# RedBeanSprout_Sch.net
KiCad netlist of a schematic drawn in Altium Designer
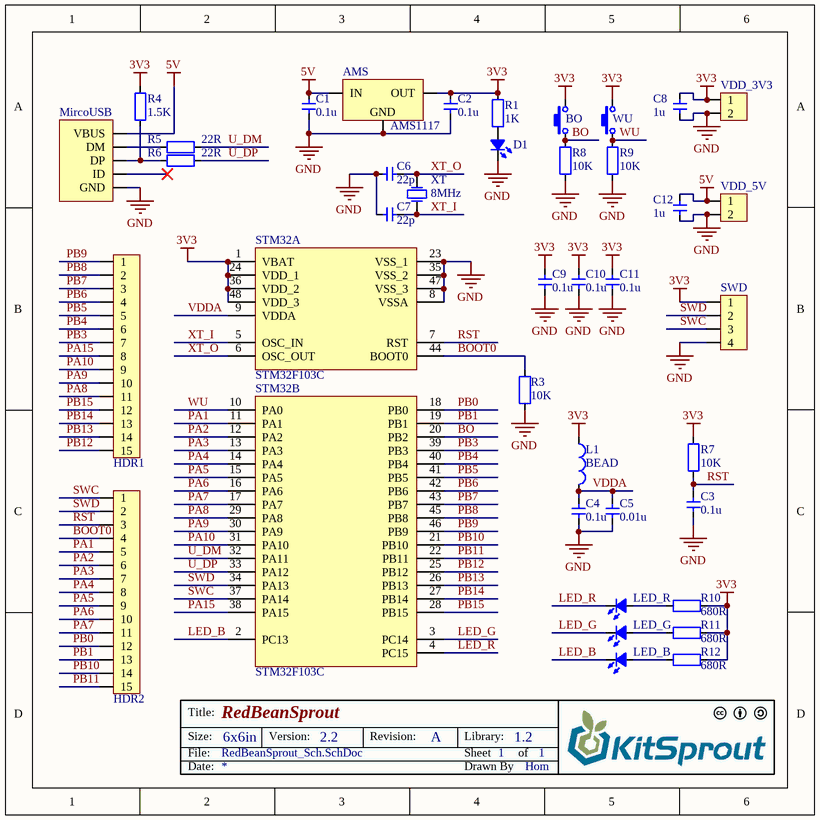
[diagram p0: RedBeanSprout_Sch.SchDoc]

(export (version "E")
  (design (tool "Eeschema 10.0.6"))
  (components
    (comp (ref "AMS")
      (value "AMS1117")
      (footprint "PCB_IntegratedCircuit:SOT223-3")
      (description "Power")
      (libsource (lib "SCH_IntegratedCircuit") (part "AMS1117"))
    )
    (comp (ref "BO")
      (value "ButtonTACT_3x6x2.5_180")
      (footprint "PCB_Switch:ButtonTACT_3x6x2.5_180")
      (description "Button")
      (libsource (lib "SCH_Switch") (part "ButtonTACT_3x6x2.5_180"))
    )
    (comp (ref "C1")
      (value "0.1u")
      (footprint "PCB_PassiveCap:CAP_0603")
      (description "Capacitor")
      (fields (field (name "Comment") "Cap_0603"))
      (libsource (lib "SCH_Passive") (part "Cap_0603"))
    )
    (comp (ref "C2")
      (value "0.1u")
      (footprint "PCB_PassiveCap:CAP_0603")
      (description "Capacitor")
      (fields (field (name "Comment") "Cap_0603"))
      (libsource (lib "SCH_Passive") (part "Cap_0603"))
    )
    (comp (ref "C3")
      (value "0.1u")
      (footprint "PCB_PassiveCap:CAP_0603")
      (description "Capacitor")
      (fields (field (name "Comment") "Cap_0603"))
      (libsource (lib "SCH_Passive") (part "Cap_0603"))
    )
    (comp (ref "C4")
      (value "0.1u")
      (footprint "PCB_PassiveCap:CAP_0603")
      (description "Capacitor")
      (fields (field (name "Comment") "Cap_0603"))
      (libsource (lib "SCH_Passive") (part "Cap_0603"))
    )
    (comp (ref "C5")
      (value "0.01u")
      (footprint "PCB_PassiveCap:CAP_0603")
      (description "Capacitor")
      (fields (field (name "Comment") "Cap_0603"))
      (libsource (lib "SCH_Passive") (part "Cap_0603"))
    )
    (comp (ref "C6")
      (value "22p")
      (footprint "PCB_PassiveCap:CAP_0603")
      (description "Capacitor")
      (fields (field (name "Comment") "Cap_0603"))
      (libsource (lib "SCH_Passive") (part "Cap_0603"))
    )
    (comp (ref "C7")
      (value "22p")
      (footprint "PCB_PassiveCap:CAP_0603")
      (description "Capacitor")
      (fields (field (name "Comment") "Cap_0603"))
      (libsource (lib "SCH_Passive") (part "Cap_0603"))
    )
    (comp (ref "C8")
      (value "1u")
      (footprint "PCB_PassiveCap:CAP_0603")
      (description "Capacitor")
      (fields (field (name "Comment") "Cap_0603"))
      (libsource (lib "SCH_Passive") (part "Cap_0603"))
    )
    (comp (ref "C9")
      (value "0.1u")
      (footprint "PCB_PassiveCap:CAP_0603")
      (description "Capacitor")
      (fields (field (name "Comment") "Cap_0603"))
      (libsource (lib "SCH_Passive") (part "Cap_0603"))
    )
    (comp (ref "C10")
      (value "0.1u")
      (footprint "PCB_PassiveCap:CAP_0603")
      (description "Capacitor")
      (fields (field (name "Comment") "Cap_0603"))
      (libsource (lib "SCH_Passive") (part "Cap_0603"))
    )
    (comp (ref "C11")
      (value "0.1u")
      (footprint "PCB_PassiveCap:CAP_0603")
      (description "Capacitor")
      (fields (field (name "Comment") "Cap_0603"))
      (libsource (lib "SCH_Passive") (part "Cap_0603"))
    )
    (comp (ref "C12")
      (value "1u")
      (footprint "PCB_PassiveCap:CAP_0603")
      (description "Capacitor")
      (fields (field (name "Comment") "Cap_0603"))
      (libsource (lib "SCH_Passive") (part "Cap_0603"))
    )
    (comp (ref "D1")
      (value "LED_0603")
      (footprint "PCB_ActiveLED:LED_0603_YELLOW")
      (description "LED")
      (libsource (lib "SCH_Active") (part "LED_0603"))
    )
    (comp (ref "HDR1")
      (value "HDR1x15_2.54")
      (footprint "PCB_ConnectorHDR:HDR1X15_2.54_180")
      (description "Header")
      (libsource (lib "SCH_ConnectorHDR") (part "HDR1x15_2.54"))
    )
    (comp (ref "HDR2")
      (value "HDR1x15_2.54")
      (footprint "PCB_ConnectorHDR:HDR1X15_2.54_180")
      (description "Header")
      (libsource (lib "SCH_ConnectorHDR") (part "HDR1x15_2.54"))
    )
    (comp (ref "L1")
      (value "BEAD")
      (footprint "PCB_PassiveInd:IND_0603")
      (description "Inductor")
      (fields (field (name "Comment") "Ind_0603"))
      (libsource (lib "SCH_Passive") (part "Ind_0603"))
    )
    (comp (ref "LED_B")
      (value "LED_0603")
      (footprint "PCB_ActiveLED:LED_0603_BLUE")
      (description "LED")
      (libsource (lib "SCH_Active") (part "LED_0603"))
    )
    (comp (ref "LED_G")
      (value "LED_0603")
      (footprint "PCB_ActiveLED:LED_0603_GREEN")
      (description "LED")
      (libsource (lib "SCH_Active") (part "LED_0603"))
    )
    (comp (ref "LED_R")
      (value "LED_0603")
      (footprint "PCB_ActiveLED:LED_0603_RED")
      (description "LED")
      (libsource (lib "SCH_Active") (part "LED_0603"))
    )
    (comp (ref "MircoUSB")
      (value "USB_Micro")
      (footprint "PCB_USB:USB_Micro-AB")
      (description "USB")
      (libsource (lib "SCH_USB") (part "USB_Micro"))
    )
    (comp (ref "R1")
      (value "1K")
      (footprint "PCB_PassiveRes:RES_0603")
      (description "Resistor")
      (fields (field (name "Comment") "Res_0603"))
      (libsource (lib "SCH_Passive") (part "Res_0603"))
    )
    (comp (ref "R3")
      (value "10K")
      (footprint "PCB_PassiveRes:RES_0603")
      (description "Resistor")
      (fields (field (name "Comment") "Res_0603"))
      (libsource (lib "SCH_Passive") (part "Res_0603"))
    )
    (comp (ref "R4")
      (value "1.5K")
      (footprint "PCB_PassiveRes:RES_0603")
      (description "Resistor")
      (fields (field (name "Comment") "Res_0603"))
      (libsource (lib "") (part "Res_0603_3"))
    )
    (comp (ref "R5")
      (value "22R")
      (footprint "PCB_PassiveRes:RES_0603")
      (description "Resistor")
      (fields (field (name "Comment") "Res_0603"))
      (libsource (lib "") (part "Res_0603_2"))
    )
    (comp (ref "R6")
      (value "22R")
      (footprint "PCB_PassiveRes:RES_0603")
      (description "Resistor")
      (fields (field (name "Comment") "Res_0603"))
      (libsource (lib "") (part "Res_0603_2"))
    )
    (comp (ref "R7")
      (value "10K")
      (footprint "PCB_PassiveRes:RES_0603")
      (description "Resistor")
      (fields (field (name "Comment") "Res_0603"))
      (libsource (lib "SCH_Passive") (part "Res_0603"))
    )
    (comp (ref "R8")
      (value "10K")
      (footprint "PCB_PassiveRes:RES_0603")
      (description "Resistor")
      (fields (field (name "Comment") "Res_0603"))
      (libsource (lib "SCH_Passive") (part "Res_0603"))
    )
    (comp (ref "R9")
      (value "10K")
      (footprint "PCB_PassiveRes:RES_0603")
      (description "Resistor")
      (fields (field (name "Comment") "Res_0603"))
      (libsource (lib "SCH_Passive") (part "Res_0603"))
    )
    (comp (ref "R10")
      (value "680R")
      (footprint "PCB_PassiveRes:RES_0603")
      (description "Resistor")
      (fields (field (name "Comment") "Res_0603"))
      (libsource (lib "") (part "Res_0603_1"))
    )
    (comp (ref "R11")
      (value "680R")
      (footprint "PCB_PassiveRes:RES_0603")
      (description "Resistor")
      (fields (field (name "Comment") "Res_0603"))
      (libsource (lib "") (part "Res_0603_1"))
    )
    (comp (ref "R12")
      (value "680R")
      (footprint "PCB_PassiveRes:RES_0603")
      (description "Resistor")
      (fields (field (name "Comment") "Res_0603"))
      (libsource (lib "") (part "Res_0603_1"))
    )
    (comp (ref "STM32")
      (value "STM32F103C")
      (footprint "PCB_IntegratedCircuit:LQFP_P0.5_48")
      (description "MCU")
      (libsource (lib "SCH_IntegratedCircuit") (part "STM32F103C"))
    )
    (comp (ref "SWD")
      (value "HDR1x4_2.54")
      (footprint "PCB_ConnectorHDR:HDR1X4_2.54_90F")
      (description "Header")
      (libsource (lib "SCH_ConnectorHDR") (part "HDR1x4_2.54"))
    )
    (comp (ref "VDD_3V3")
      (value "HDR1x2_2.54")
      (footprint "PCB_ConnectorHDR:HDR1X2_2.54_180")
      (description "Header")
      (libsource (lib "SCH_ConnectorHDR") (part "HDR1x2_2.54"))
    )
    (comp (ref "VDD_5V")
      (value "HDR1x2_2.54")
      (footprint "PCB_ConnectorHDR:HDR1X2_2.54_180")
      (description "Header")
      (libsource (lib "SCH_ConnectorHDR") (part "HDR1x2_2.54"))
    )
    (comp (ref "WU")
      (value "ButtonTACT_3x6x2.5_180")
      (footprint "PCB_Switch:ButtonTACT_3x6x2.5_180")
      (description "Button")
      (libsource (lib "SCH_Switch") (part "ButtonTACT_3x6x2.5_180"))
    )
    (comp (ref "XT")
      (value "8MHz")
      (footprint "PCB_Oscillator:XT_5032_2")
      (description "Crystal Oscillator")
      (fields (field (name "Comment") "XTAL_5032_2P"))
      (libsource (lib "SCH_Oscillator") (part "XTAL_5032_2P"))
    )
  )
  (nets
    (net (code "1") (name "/BO") (class "Default")
      (node (ref "BO") (pin "1") (pinfunction "1_1") (pintype "passive"))
      (node (ref "R8") (pin "2") (pinfunction "2_2") (pintype "passive"))
      (node (ref "STM32") (pin "20") (pinfunction "PB2_20") (pintype "passive"))
    )
    (net (code "2") (name "/BOOT0") (class "Default")
      (node (ref "HDR2") (pin "4") (pinfunction "4_4") (pintype "passive"))
      (node (ref "R3") (pin "2") (pinfunction "2_2") (pintype "passive"))
      (node (ref "STM32") (pin "44") (pinfunction "BOOT0_44") (pintype "passive"))
    )
    (net (code "3") (name "/LED_B") (class "Default")
      (node (ref "LED_B") (pin "2") (pinfunction "K_2") (pintype "passive"))
      (node (ref "STM32") (pin "2") (pinfunction "PC13_2") (pintype "passive"))
    )
    (net (code "4") (name "/LED_G") (class "Default")
      (node (ref "LED_G") (pin "2") (pinfunction "K_2") (pintype "passive"))
      (node (ref "STM32") (pin "3") (pinfunction "PC14_3") (pintype "passive"))
    )
    (net (code "5") (name "/LED_R") (class "Default")
      (node (ref "LED_R") (pin "2") (pinfunction "K_2") (pintype "passive"))
      (node (ref "STM32") (pin "4") (pinfunction "PC15_4") (pintype "passive"))
    )
    (net (code "6") (name "/PA1") (class "Default")
      (node (ref "HDR2") (pin "5") (pinfunction "5_5") (pintype "passive"))
      (node (ref "STM32") (pin "11") (pinfunction "PA1_11") (pintype "passive"))
    )
    (net (code "7") (name "/PA2") (class "Default")
      (node (ref "HDR2") (pin "6") (pinfunction "6_6") (pintype "passive"))
      (node (ref "STM32") (pin "12") (pinfunction "PA2_12") (pintype "passive"))
    )
    (net (code "8") (name "/PA3") (class "Default")
      (node (ref "HDR2") (pin "7") (pinfunction "7_7") (pintype "passive"))
      (node (ref "STM32") (pin "13") (pinfunction "PA3_13") (pintype "passive"))
    )
    (net (code "9") (name "/PA4") (class "Default")
      (node (ref "HDR2") (pin "8") (pinfunction "8_8") (pintype "passive"))
      (node (ref "STM32") (pin "14") (pinfunction "PA4_14") (pintype "passive"))
    )
    (net (code "10") (name "/PA5") (class "Default")
      (node (ref "HDR2") (pin "9") (pinfunction "9_9") (pintype "passive"))
      (node (ref "STM32") (pin "15") (pinfunction "PA5_15") (pintype "passive"))
    )
    (net (code "11") (name "/PA6") (class "Default")
      (node (ref "HDR2") (pin "10") (pinfunction "10_10") (pintype "passive"))
      (node (ref "STM32") (pin "16") (pinfunction "PA6_16") (pintype "passive"))
    )
    (net (code "12") (name "/PA7") (class "Default")
      (node (ref "HDR2") (pin "11") (pinfunction "11_11") (pintype "passive"))
      (node (ref "STM32") (pin "17") (pinfunction "PA7_17") (pintype "passive"))
    )
    (net (code "13") (name "/PA8") (class "Default")
      (node (ref "HDR1") (pin "11") (pinfunction "11_11") (pintype "passive"))
      (node (ref "STM32") (pin "29") (pinfunction "PA8_29") (pintype "passive"))
    )
    (net (code "14") (name "/PA9") (class "Default")
      (node (ref "HDR1") (pin "10") (pinfunction "10_10") (pintype "passive"))
      (node (ref "STM32") (pin "30") (pinfunction "PA9_30") (pintype "passive"))
    )
    (net (code "15") (name "/PA10") (class "Default")
      (node (ref "HDR1") (pin "9") (pinfunction "9_9") (pintype "passive"))
      (node (ref "STM32") (pin "31") (pinfunction "PA10_31") (pintype "passive"))
    )
    (net (code "16") (name "/PA15") (class "Default")
      (node (ref "HDR1") (pin "8") (pinfunction "8_8") (pintype "passive"))
      (node (ref "STM32") (pin "38") (pinfunction "PA15_38") (pintype "passive"))
    )
    (net (code "17") (name "/PB0") (class "Default")
      (node (ref "HDR2") (pin "12") (pinfunction "12_12") (pintype "passive"))
      (node (ref "STM32") (pin "18") (pinfunction "PB0_18") (pintype "passive"))
    )
    (net (code "18") (name "/PB1") (class "Default")
      (node (ref "HDR2") (pin "13") (pinfunction "13_13") (pintype "passive"))
      (node (ref "STM32") (pin "19") (pinfunction "PB1_19") (pintype "passive"))
    )
    (net (code "19") (name "/PB3") (class "Default")
      (node (ref "HDR1") (pin "7") (pinfunction "7_7") (pintype "passive"))
      (node (ref "STM32") (pin "39") (pinfunction "PB3_39") (pintype "passive"))
    )
    (net (code "20") (name "/PB4") (class "Default")
      (node (ref "HDR1") (pin "6") (pinfunction "6_6") (pintype "passive"))
      (node (ref "STM32") (pin "40") (pinfunction "PB4_40") (pintype "passive"))
    )
    (net (code "21") (name "/PB5") (class "Default")
      (node (ref "HDR1") (pin "5") (pinfunction "5_5") (pintype "passive"))
      (node (ref "STM32") (pin "41") (pinfunction "PB5_41") (pintype "passive"))
    )
    (net (code "22") (name "/PB6") (class "Default")
      (node (ref "HDR1") (pin "4") (pinfunction "4_4") (pintype "passive"))
      (node (ref "STM32") (pin "42") (pinfunction "PB6_42") (pintype "passive"))
    )
    (net (code "23") (name "/PB7") (class "Default")
      (node (ref "HDR1") (pin "3") (pinfunction "3_3") (pintype "passive"))
      (node (ref "STM32") (pin "43") (pinfunction "PB7_43") (pintype "passive"))
    )
    (net (code "24") (name "/PB8") (class "Default")
      (node (ref "HDR1") (pin "2") (pinfunction "2_2") (pintype "passive"))
      (node (ref "STM32") (pin "45") (pinfunction "PB8_45") (pintype "passive"))
    )
    (net (code "25") (name "/PB9") (class "Default")
      (node (ref "HDR1") (pin "1") (pinfunction "1_1") (pintype "passive"))
      (node (ref "STM32") (pin "46") (pinfunction "PB9_46") (pintype "passive"))
    )
    (net (code "26") (name "/PB10") (class "Default")
      (node (ref "HDR2") (pin "14") (pinfunction "14_14") (pintype "passive"))
      (node (ref "STM32") (pin "21") (pinfunction "PB10_21") (pintype "passive"))
    )
    (net (code "27") (name "/PB11") (class "Default")
      (node (ref "HDR2") (pin "15") (pinfunction "15_15") (pintype "passive"))
      (node (ref "STM32") (pin "22") (pinfunction "PB11_22") (pintype "passive"))
    )
    (net (code "28") (name "/PB12") (class "Default")
      (node (ref "HDR1") (pin "15") (pinfunction "15_15") (pintype "passive"))
      (node (ref "STM32") (pin "25") (pinfunction "PB12_25") (pintype "passive"))
    )
    (net (code "29") (name "/PB13") (class "Default")
      (node (ref "HDR1") (pin "14") (pinfunction "14_14") (pintype "passive"))
      (node (ref "STM32") (pin "26") (pinfunction "PB13_26") (pintype "passive"))
    )
    (net (code "30") (name "/PB14") (class "Default")
      (node (ref "HDR1") (pin "13") (pinfunction "13_13") (pintype "passive"))
      (node (ref "STM32") (pin "27") (pinfunction "PB14_27") (pintype "passive"))
    )
    (net (code "31") (name "/PB15") (class "Default")
      (node (ref "HDR1") (pin "12") (pinfunction "12_12") (pintype "passive"))
      (node (ref "STM32") (pin "28") (pinfunction "PB15_28") (pintype "passive"))
    )
    (net (code "32") (name "/RST") (class "Default")
      (node (ref "C3") (pin "2") (pinfunction "2_2") (pintype "passive"))
      (node (ref "HDR2") (pin "3") (pinfunction "3_3") (pintype "passive"))
      (node (ref "R7") (pin "1") (pinfunction "1_1") (pintype "passive"))
      (node (ref "STM32") (pin "7") (pinfunction "RST_7") (pintype "passive"))
    )
    (net (code "33") (name "/SWC") (class "Default")
      (node (ref "HDR2") (pin "1") (pinfunction "1_1") (pintype "passive"))
      (node (ref "STM32") (pin "37") (pinfunction "PA14_37") (pintype "passive"))
      (node (ref "SWD") (pin "3") (pinfunction "3_3") (pintype "passive"))
    )
    (net (code "34") (name "/SWD") (class "Default")
      (node (ref "HDR2") (pin "2") (pinfunction "2_2") (pintype "passive"))
      (node (ref "STM32") (pin "34") (pinfunction "PA13_34") (pintype "passive"))
      (node (ref "SWD") (pin "2") (pinfunction "2_2") (pintype "passive"))
    )
    (net (code "35") (name "/U_DM") (class "Default")
      (node (ref "R5") (pin "2") (pinfunction "2_2") (pintype "passive"))
      (node (ref "STM32") (pin "32") (pinfunction "PA11_32") (pintype "passive"))
    )
    (net (code "36") (name "/U_DP") (class "Default")
      (node (ref "R6") (pin "2") (pinfunction "2_2") (pintype "passive"))
      (node (ref "STM32") (pin "33") (pinfunction "PA12_33") (pintype "passive"))
    )
    (net (code "37") (name "/VDDA") (class "Default")
      (node (ref "C4") (pin "2") (pinfunction "2_2") (pintype "passive"))
      (node (ref "C5") (pin "2") (pinfunction "2_2") (pintype "passive"))
      (node (ref "L1") (pin "2") (pinfunction "2_2") (pintype "passive"))
      (node (ref "STM32") (pin "9") (pinfunction "VDDA_9") (pintype "passive"))
    )
    (net (code "38") (name "/WU") (class "Default")
      (node (ref "R9") (pin "2") (pinfunction "2_2") (pintype "passive"))
      (node (ref "STM32") (pin "10") (pinfunction "PA0_10") (pintype "passive"))
      (node (ref "WU") (pin "1") (pinfunction "1_1") (pintype "passive"))
    )
    (net (code "39") (name "/XT_I") (class "Default")
      (node (ref "C7") (pin "1") (pinfunction "1_1") (pintype "passive"))
      (node (ref "STM32") (pin "5") (pinfunction "OSC_IN_5") (pintype "passive"))
      (node (ref "XT") (pin "1") (pinfunction "OSC1_1") (pintype "passive"))
    )
    (net (code "40") (name "/XT_O") (class "Default")
      (node (ref "C6") (pin "1") (pinfunction "1_1") (pintype "passive"))
      (node (ref "STM32") (pin "6") (pinfunction "OSC_OUT_6") (pintype "passive"))
      (node (ref "XT") (pin "2") (pinfunction "OSC2_2") (pintype "passive"))
    )
    (net (code "41") (name "3V3") (class "Default")
      (node (ref "AMS") (pin "2") (pinfunction "OUT_2") (pintype "power_in"))
      (node (ref "BO") (pin "2") (pinfunction "2_2") (pintype "passive"))
      (node (ref "C10") (pin "2") (pinfunction "2_2") (pintype "passive"))
      (node (ref "C11") (pin "2") (pinfunction "2_2") (pintype "passive"))
      (node (ref "C2") (pin "2") (pinfunction "2_2") (pintype "passive"))
      (node (ref "C8") (pin "2") (pinfunction "2_2") (pintype "passive"))
      (node (ref "C9") (pin "2") (pinfunction "2_2") (pintype "passive"))
      (node (ref "L1") (pin "1") (pinfunction "1_1") (pintype "passive"))
      (node (ref "R1") (pin "2") (pinfunction "2_2") (pintype "passive"))
      (node (ref "R10") (pin "1") (pinfunction "1_1") (pintype "passive"))
      (node (ref "R11") (pin "1") (pinfunction "1_1") (pintype "passive"))
      (node (ref "R12") (pin "1") (pinfunction "1_1") (pintype "passive"))
      (node (ref "R4") (pin "1") (pinfunction "1_1") (pintype "passive"))
      (node (ref "R7") (pin "2") (pinfunction "2_2") (pintype "passive"))
      (node (ref "STM32") (pin "1") (pinfunction "VBAT_1") (pintype "passive"))
      (node (ref "STM32") (pin "24") (pinfunction "VDD_1_24") (pintype "passive"))
      (node (ref "STM32") (pin "36") (pinfunction "VDD_2_36") (pintype "passive"))
      (node (ref "STM32") (pin "48") (pinfunction "VDD_3_48") (pintype "passive"))
      (node (ref "SWD") (pin "1") (pinfunction "1_1") (pintype "passive"))
      (node (ref "VDD_3V3") (pin "1") (pinfunction "1_1") (pintype "passive"))
      (node (ref "WU") (pin "2") (pinfunction "2_2") (pintype "passive"))
    )
    (net (code "42") (name "5V") (class "Default")
      (node (ref "AMS") (pin "3") (pinfunction "IN_3") (pintype "power_in"))
      (node (ref "C1") (pin "2") (pinfunction "2_2") (pintype "passive"))
      (node (ref "C12") (pin "2") (pinfunction "2_2") (pintype "passive"))
      (node (ref "MircoUSB") (pin "1") (pinfunction "VBUS_1") (pintype "passive"))
      (node (ref "VDD_5V") (pin "1") (pinfunction "1_1") (pintype "passive"))
    )
    (net (code "43") (name "GND") (class "Default")
      (node (ref "AMS") (pin "1") (pinfunction "GND_1") (pintype "power_in"))
      (node (ref "C1") (pin "1") (pinfunction "1_1") (pintype "passive"))
      (node (ref "C10") (pin "1") (pinfunction "1_1") (pintype "passive"))
      (node (ref "C11") (pin "1") (pinfunction "1_1") (pintype "passive"))
      (node (ref "C12") (pin "1") (pinfunction "1_1") (pintype "passive"))
      (node (ref "C2") (pin "1") (pinfunction "1_1") (pintype "passive"))
      (node (ref "C3") (pin "1") (pinfunction "1_1") (pintype "passive"))
      (node (ref "C4") (pin "1") (pinfunction "1_1") (pintype "passive"))
      (node (ref "C5") (pin "1") (pinfunction "1_1") (pintype "passive"))
      (node (ref "C6") (pin "2") (pinfunction "2_2") (pintype "passive"))
      (node (ref "C7") (pin "2") (pinfunction "2_2") (pintype "passive"))
      (node (ref "C8") (pin "1") (pinfunction "1_1") (pintype "passive"))
      (node (ref "C9") (pin "1") (pinfunction "1_1") (pintype "passive"))
      (node (ref "D1") (pin "2") (pinfunction "K_2") (pintype "passive"))
      (node (ref "MircoUSB") (pin "5") (pinfunction "GND_5") (pintype "passive"))
      (node (ref "R3") (pin "1") (pinfunction "1_1") (pintype "passive"))
      (node (ref "R8") (pin "1") (pinfunction "1_1") (pintype "passive"))
      (node (ref "R9") (pin "1") (pinfunction "1_1") (pintype "passive"))
      (node (ref "STM32") (pin "23") (pinfunction "VSS_1_23") (pintype "passive"))
      (node (ref "STM32") (pin "35") (pinfunction "VSS_2_35") (pintype "passive"))
      (node (ref "STM32") (pin "47") (pinfunction "VSS_3_47") (pintype "passive"))
      (node (ref "STM32") (pin "8") (pinfunction "VSSA_8") (pintype "passive"))
      (node (ref "SWD") (pin "4") (pinfunction "4_4") (pintype "passive"))
      (node (ref "VDD_3V3") (pin "2") (pinfunction "2_2") (pintype "passive"))
      (node (ref "VDD_5V") (pin "2") (pinfunction "2_2") (pintype "passive"))
    )
    (net (code "44") (name "Net-(D1-A)") (class "Default")
      (node (ref "D1") (pin "1") (pinfunction "A_1") (pintype "passive"))
      (node (ref "R1") (pin "1") (pinfunction "1_1") (pintype "passive"))
    )
    (net (code "45") (name "Net-(LED_B-A)") (class "Default")
      (node (ref "LED_B") (pin "1") (pinfunction "A_1") (pintype "passive"))
      (node (ref "R12") (pin "2") (pinfunction "2_2") (pintype "passive"))
    )
    (net (code "46") (name "Net-(LED_G-A)") (class "Default")
      (node (ref "LED_G") (pin "1") (pinfunction "A_1") (pintype "passive"))
      (node (ref "R11") (pin "2") (pinfunction "2_2") (pintype "passive"))
    )
    (net (code "47") (name "Net-(LED_R-A)") (class "Default")
      (node (ref "LED_R") (pin "1") (pinfunction "A_1") (pintype "passive"))
      (node (ref "R10") (pin "2") (pinfunction "2_2") (pintype "passive"))
    )
    (net (code "48") (name "Net-(MircoUSB-DM)") (class "Default")
      (node (ref "MircoUSB") (pin "2") (pinfunction "DM_2") (pintype "passive"))
      (node (ref "R5") (pin "1") (pinfunction "1_1") (pintype "passive"))
    )
    (net (code "49") (name "Net-(MircoUSB-DP)") (class "Default")
      (node (ref "MircoUSB") (pin "3") (pinfunction "DP_3") (pintype "passive"))
      (node (ref "R4") (pin "2") (pinfunction "2_2") (pintype "passive"))
      (node (ref "R6") (pin "1") (pinfunction "1_1") (pintype "passive"))
    )
    (net (code "50") (name "unconnected-(MircoUSB-ID-Pad4)") (class "Default")
      (node (ref "MircoUSB") (pin "4") (pinfunction "ID_4") (pintype "passive+no_connect"))
    )
  )
)
